# jha_sensor.net
KiCad netlist of a schematic drawn in EAGLE
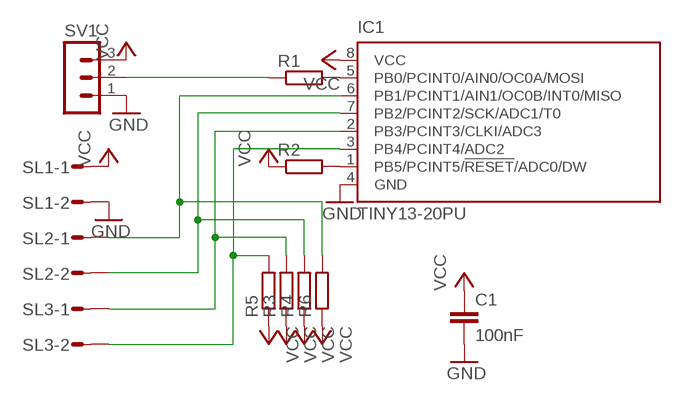
[diagram p0: schematic, sheet 1]

(export (version "E")
  (design (tool "Eeschema 10.0.6"))
  (components
    (comp (ref "C1")
      (value "100nF")
      (footprint "eagle-import:C0603")
      (libsource (lib "eagle-import") (part "C-EUC0603"))
    )
    (comp (ref "IC1")
      (value "TINY13-20PU")
      (footprint "eagle-import:DIL08")
      (fields
        (field (name "MPN") "ATTINY13-20PU")
        (field (name "MPN_1") "ATTINY13-20PU")
        (field (name "OC_FARNELL") "9171550")
        (field (name "OC_NEWARK") "96K6521")
      )
      (libsource (lib "eagle-import") (part "TINY13PU-20"))
    )
    (comp (ref "R1")
      (value "R-EU_R0805")
      (footprint "eagle-import:R0805")
      (libsource (lib "eagle-import") (part "R-EU_R0805"))
    )
    (comp (ref "R2")
      (value "R-EU_R0805")
      (footprint "eagle-import:R0805")
      (libsource (lib "eagle-import") (part "R-EU_R0805"))
    )
    (comp (ref "R3")
      (value "R-EU_R0805")
      (footprint "eagle-import:R0805")
      (libsource (lib "eagle-import") (part "R-EU_R0805"))
    )
    (comp (ref "R4")
      (value "R-EU_R0805")
      (footprint "eagle-import:R0805")
      (libsource (lib "eagle-import") (part "R-EU_R0805"))
    )
    (comp (ref "R5")
      (value "R-EU_R0805")
      (footprint "eagle-import:R0805")
      (libsource (lib "eagle-import") (part "R-EU_R0805"))
    )
    (comp (ref "R6")
      (value "R-EU_R0805")
      (footprint "eagle-import:R0805")
      (libsource (lib "eagle-import") (part "R-EU_R0805"))
    )
    (comp (ref "SL1")
      (value "MA02S")
      (footprint "eagle-import:02PA")
      (libsource (lib "eagle-import") (part "MA02S"))
    )
    (comp (ref "SL2")
      (value "MA02S")
      (footprint "eagle-import:02PA")
      (libsource (lib "eagle-import") (part "MA02S"))
    )
    (comp (ref "SL3")
      (value "MA02S")
      (footprint "eagle-import:02PA")
      (libsource (lib "eagle-import") (part "MA02S"))
    )
    (comp (ref "SV1")
      (value "MA03-1")
      (footprint "eagle-import:MA03-1")
      (libsource (lib "eagle-import") (part "MA03-1"))
    )
  )
  (nets
    (net (code "1") (name "GND") (class "Default")
      (node (ref "C1") (pin "2") (pinfunction "2_2") (pintype "passive"))
      (node (ref "IC1") (pin "4") (pinfunction "GND_4") (pintype "power_in"))
      (node (ref "SL1") (pin "2") (pinfunction "S_2") (pintype "passive"))
      (node (ref "SV1") (pin "1") (pinfunction "1_1") (pintype "passive"))
    )
    (net (code "2") (name "Net-(IC1-PB0{slash}PCINT0{slash}AIN0{slash}OC0A{slash}MOSI)") (class "Default")
      (node (ref "IC1") (pin "5") (pinfunction "PB0/PCINT0/AIN0/OC0A/MOSI_5") (pintype "bidirectional"))
      (node (ref "R1") (pin "2") (pinfunction "2_2") (pintype "passive"))
    )
    (net (code "3") (name "Net-(IC1-PB1{slash}PCINT1{slash}AIN1{slash}OC0B{slash}INT0{slash}MISO)") (class "Default")
      (node (ref "IC1") (pin "6") (pinfunction "PB1/PCINT1/AIN1/OC0B/INT0/MISO_6") (pintype "bidirectional"))
      (node (ref "R6") (pin "2") (pinfunction "2_2") (pintype "passive"))
      (node (ref "SL2") (pin "1") (pinfunction "S_1") (pintype "passive"))
    )
    (net (code "4") (name "Net-(IC1-PB2{slash}PCINT2{slash}SCK{slash}ADC1{slash}T0)") (class "Default")
      (node (ref "IC1") (pin "7") (pinfunction "PB2/PCINT2/SCK/ADC1/T0_7") (pintype "bidirectional"))
      (node (ref "R4") (pin "2") (pinfunction "2_2") (pintype "passive"))
      (node (ref "SL2") (pin "2") (pinfunction "S_2") (pintype "passive"))
    )
    (net (code "5") (name "Net-(IC1-PB3{slash}PCINT3{slash}CLKI{slash}ADC3)") (class "Default")
      (node (ref "IC1") (pin "2") (pinfunction "PB3/PCINT3/CLKI/ADC3_2") (pintype "bidirectional"))
      (node (ref "R3") (pin "2") (pinfunction "2_2") (pintype "passive"))
      (node (ref "SL3") (pin "1") (pinfunction "S_1") (pintype "passive"))
    )
    (net (code "6") (name "Net-(IC1-PB4{slash}PCINT4{slash}ADC2)") (class "Default")
      (node (ref "IC1") (pin "3") (pinfunction "PB4/PCINT4/ADC2_3") (pintype "bidirectional"))
      (node (ref "R5") (pin "2") (pinfunction "2_2") (pintype "passive"))
      (node (ref "SL3") (pin "2") (pinfunction "S_2") (pintype "passive"))
    )
    (net (code "7") (name "Net-(IC1-PB5{slash}PCINT5{slash}~{RESET}{slash}ADC0{slash}DW)") (class "Default")
      (node (ref "IC1") (pin "1") (pinfunction "PB5/PCINT5/~{RESET}/ADC0/DW_1") (pintype "bidirectional"))
      (node (ref "R2") (pin "2") (pinfunction "2_2") (pintype "passive"))
    )
    (net (code "8") (name "Net-(R1-Pad1)") (class "Default")
      (node (ref "R1") (pin "1") (pinfunction "1_1") (pintype "passive"))
      (node (ref "SV1") (pin "2") (pinfunction "2_2") (pintype "passive"))
    )
    (net (code "9") (name "VCC") (class "Default")
      (node (ref "C1") (pin "1") (pinfunction "1_1") (pintype "passive"))
      (node (ref "IC1") (pin "8") (pinfunction "VCC_8") (pintype "power_in"))
      (node (ref "R2") (pin "1") (pinfunction "1_1") (pintype "passive"))
      (node (ref "R3") (pin "1") (pinfunction "1_1") (pintype "passive"))
      (node (ref "R4") (pin "1") (pinfunction "1_1") (pintype "passive"))
      (node (ref "R5") (pin "1") (pinfunction "1_1") (pintype "passive"))
      (node (ref "R6") (pin "1") (pinfunction "1_1") (pintype "passive"))
      (node (ref "SL1") (pin "1") (pinfunction "S_1") (pintype "passive"))
      (node (ref "SV1") (pin "3") (pinfunction "3_3") (pintype "passive"))
    )
  )
)
